# ADC_AH.net
KiCad netlist of a schematic drawn in Altium Designer
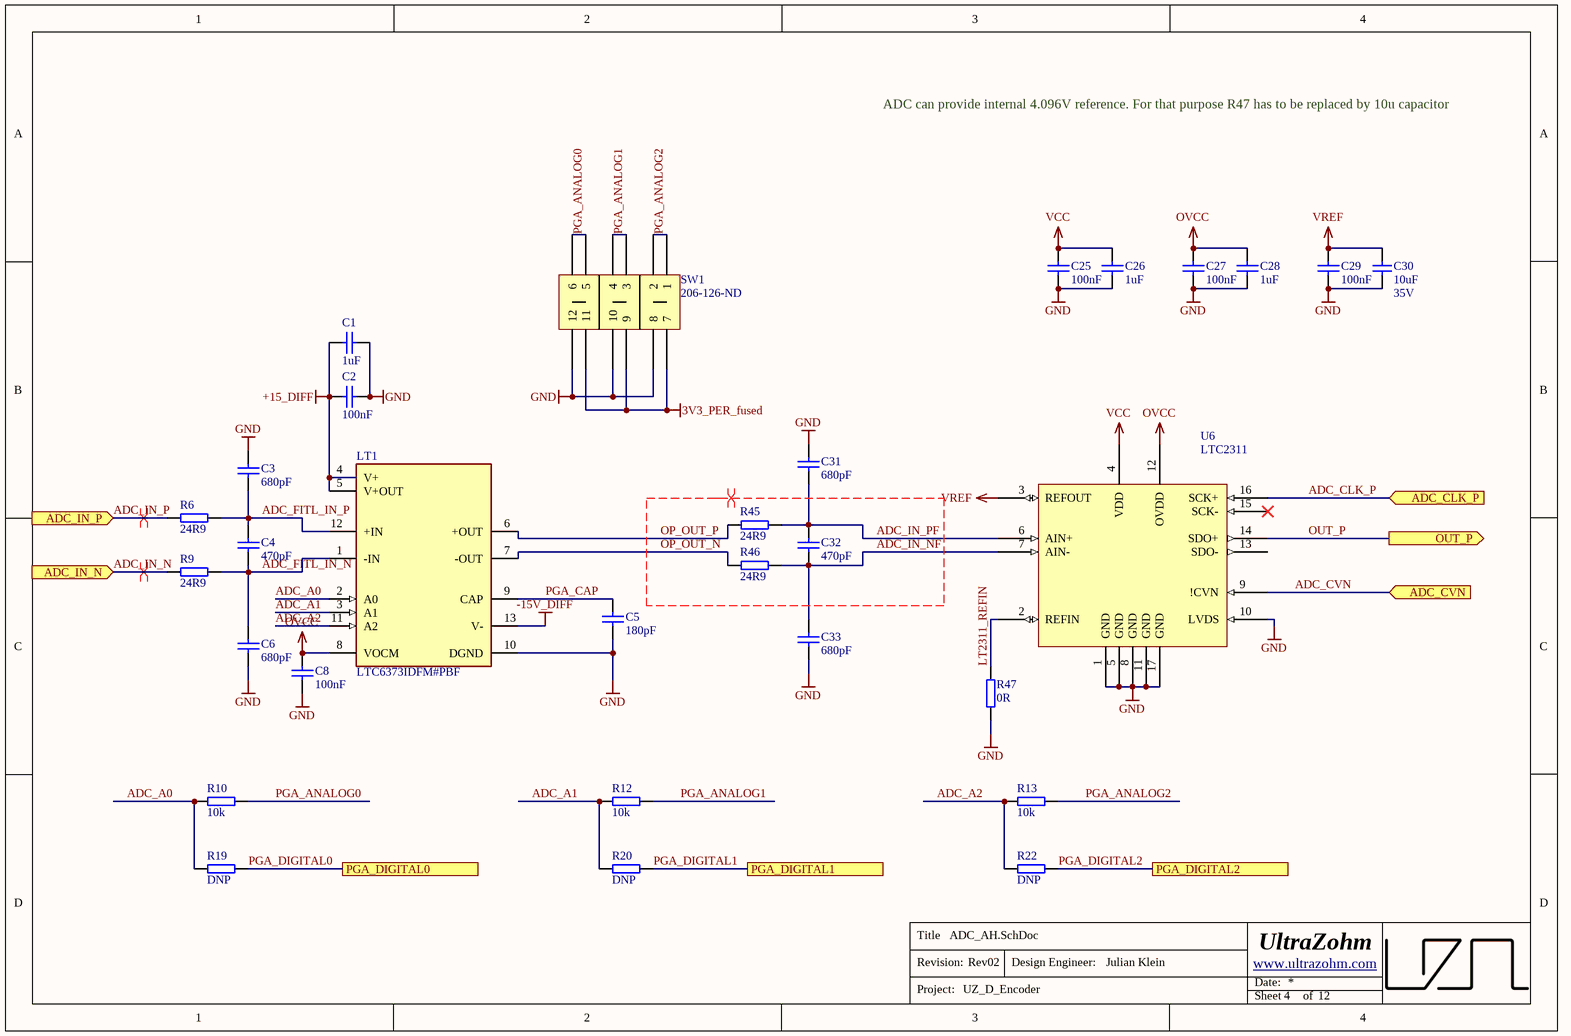
[diagram p0: ADC_AH.SchDoc]

(export (version "E")
  (design (tool "Eeschema 10.0.6"))
  (components
    (comp (ref "C1")
      (value "1uF")
      (footprint "CAPC1608X07N")
      (fields (field (name "MPN") "C0603C105K3R") (field (name "VOLTAGE") "25V"))
      (libsource (lib "UltraZohm_ADC") (part "Cap_0603"))
    )
    (comp (ref "C2")
      (value "100nF")
      (footprint "CAPC1608X07N")
      (fields (field (name "MF") "Würth") (field (name "MPN") "885012206071") (field (name "VOLTAGE") "25V"))
      (libsource (lib "UltraZohm_ADC") (part "Cap_0603"))
    )
    (comp (ref "C3")
      (value "680pF")
      (footprint "CAPC1608X07N")
      (fields
        (field (name "MF") "Vishay")
        (field (name "MPN") "VJ0603A681GXJCW1BC")
        (field (name "VOLTAGE") "16V")
      )
      (libsource (lib "UltraZohm_ADC") (part "Cap_0603"))
    )
    (comp (ref "C4")
      (value "470pF")
      (footprint "CAPC1608X07N")
      (fields
        (field (name "MF") "Vishay")
        (field (name "MPN") "VJ0603A471GXJPW1BC")
        (field (name "VOLTAGE") "16V")
      )
      (libsource (lib "UltraZohm_ADC") (part "Cap_0603"))
    )
    (comp (ref "C5")
      (value "180pF")
      (footprint "CAPC1608X07N")
      (fields
        (field (name "MF") "Vishay")
        (field (name "MPN") "VJ0603A681GXJCW1BC")
        (field (name "VOLTAGE") "16V")
      )
      (libsource (lib "UltraZohm_ADC") (part "Cap_0603"))
    )
    (comp (ref "C6")
      (value "680pF")
      (footprint "CAPC1608X07N")
      (fields
        (field (name "MF") "Vishay")
        (field (name "MPN") "VJ0603A681GXJCW1BC")
        (field (name "VOLTAGE") "16V")
      )
      (libsource (lib "UltraZohm_ADC") (part "Cap_0603"))
    )
    (comp (ref "C8")
      (value "100nF")
      (footprint "CAPC1608X07N")
      (fields (field (name "MF") "Würth") (field (name "MPN") "885012206071") (field (name "VOLTAGE") "25V"))
      (libsource (lib "UltraZohm_ADC") (part "Cap_0603"))
    )
    (comp (ref "C25")
      (value "100nF")
      (footprint "CAPC1608X07N")
      (fields (field (name "MF") "Würth") (field (name "MPN") "885012206071") (field (name "VOLTAGE") "25V"))
      (libsource (lib "UltraZohm_ADC") (part "Cap_0603"))
    )
    (comp (ref "C26")
      (value "1uF")
      (footprint "CAPC1608X07N")
      (fields (field (name "MPN") "C0603C105K3R") (field (name "VOLTAGE") "25V"))
      (libsource (lib "UltraZohm_ADC") (part "Cap_0603"))
    )
    (comp (ref "C27")
      (value "100nF")
      (footprint "CAPC1608X07N")
      (fields (field (name "MF") "Würth") (field (name "MPN") "885012206071") (field (name "VOLTAGE") "25V"))
      (libsource (lib "UltraZohm_ADC") (part "Cap_0603"))
    )
    (comp (ref "C28")
      (value "1uF")
      (footprint "CAPC1608X07N")
      (fields (field (name "MPN") "C0603C105K3R") (field (name "VOLTAGE") "25V"))
      (libsource (lib "UltraZohm_ADC") (part "Cap_0603"))
    )
    (comp (ref "C29")
      (value "100nF")
      (footprint "CAPC1608X07N")
      (fields (field (name "MF") "Würth") (field (name "MPN") "885012206071") (field (name "VOLTAGE") "25V"))
      (libsource (lib "UltraZohm_ADC") (part "Cap_0603"))
    )
    (comp (ref "C30")
      (value "10uF")
      (footprint "C_1206")
      (description "Capacitor 1206")
      (fields
        (field (name "TOLERANCE") "10%")
        (field (name "MF") "Murata Electronics")
        (field (name "VOLTAGE") "35V")
        (field (name "CREATED") "2018_06_25_AGeiger")
      )
      (libsource (lib "UltraZohm_ADC") (part "C_1206"))
    )
    (comp (ref "C31")
      (value "680pF")
      (footprint "CAPC1608X07N")
      (fields
        (field (name "MF") "Vishay")
        (field (name "MPN") "VJ0603A681GXJCW1BC")
        (field (name "VOLTAGE") "16V")
      )
      (libsource (lib "UltraZohm_ADC") (part "Cap_0603"))
    )
    (comp (ref "C32")
      (value "470pF")
      (footprint "CAPC1608X07N")
      (fields
        (field (name "MF") "Vishay")
        (field (name "MPN") "VJ0603A471GXJPW1BC")
        (field (name "VOLTAGE") "16V")
      )
      (libsource (lib "UltraZohm_ADC") (part "Cap_0603"))
    )
    (comp (ref "C33")
      (value "680pF")
      (footprint "CAPC1608X07N")
      (fields
        (field (name "MF") "Vishay")
        (field (name "MPN") "VJ0603A681GXJCW1BC")
        (field (name "VOLTAGE") "16V")
      )
      (libsource (lib "UltraZohm_ADC") (part "Cap_0603"))
    )
    (comp (ref "LT1")
      (value "LTC6373IDFM#PBF")
      (footprint "FP-LTC6373IDFM#PBF-MFG")
      (description "INST Amp Single ±18V 12-Pin DFN EP Tube")
      (libsource (lib "Altium Content Vault") (part "8e72af7b36638ae68c50ab628123914"))
    )
    (comp (ref "R6")
      (value "24R9")
      (footprint "RESC1608X06N")
      (fields (field (name "MF") "Yageo") (field (name "MPN") "RC0603FR-0724R9L"))
      (libsource (lib "UltraZohm_ADC") (part "R_0603"))
    )
    (comp (ref "R9")
      (value "24R9")
      (footprint "RESC1608X06N")
      (fields (field (name "MF") "Yageo") (field (name "MPN") "RC0603FR-0724R9L"))
      (libsource (lib "UltraZohm_ADC") (part "R_0603"))
    )
    (comp (ref "R10")
      (value "10k")
      (footprint "RESC1608X06N")
      (fields (field (name "MF") "Vishay") (field (name "MPN") "CRCW06030000Z0EAC"))
      (libsource (lib "UltraZohm_ADC") (part "R_0603"))
    )
    (comp (ref "R12")
      (value "10k")
      (footprint "RESC1608X06N")
      (fields (field (name "MF") "Vishay") (field (name "MPN") "CRCW06030000Z0EAC"))
      (libsource (lib "UltraZohm_ADC") (part "R_0603"))
    )
    (comp (ref "R13")
      (value "10k")
      (footprint "RESC1608X06N")
      (fields (field (name "MF") "Vishay") (field (name "MPN") "CRCW06030000Z0EAC"))
      (libsource (lib "UltraZohm_ADC") (part "R_0603"))
    )
    (comp (ref "R19")
      (value "DNP")
      (footprint "RESC1608X06N")
      (fields (field (name "MF") "Vishay") (field (name "MPN") "CRCW06030000Z0EAC"))
      (libsource (lib "UltraZohm_ADC") (part "R_0603"))
    )
    (comp (ref "R20")
      (value "DNP")
      (footprint "RESC1608X06N")
      (fields (field (name "MF") "Vishay") (field (name "MPN") "CRCW06030000Z0EAC"))
      (libsource (lib "UltraZohm_ADC") (part "R_0603"))
    )
    (comp (ref "R22")
      (value "DNP")
      (footprint "RESC1608X06N")
      (fields (field (name "MF") "Vishay") (field (name "MPN") "CRCW06030000Z0EAC"))
      (libsource (lib "UltraZohm_ADC") (part "R_0603"))
    )
    (comp (ref "R45")
      (value "24R9")
      (footprint "RESC1608X06N")
      (fields (field (name "MF") "Yageo") (field (name "MPN") "RC0603FR-0724R9L"))
      (libsource (lib "UltraZohm_ADC") (part "R_0603"))
    )
    (comp (ref "R46")
      (value "24R9")
      (footprint "RESC1608X06N")
      (fields (field (name "MF") "Yageo") (field (name "MPN") "RC0603FR-0724R9L"))
      (libsource (lib "UltraZohm_ADC") (part "R_0603"))
    )
    (comp (ref "R47")
      (value "0R")
      (footprint "RESC1608X06N")
      (fields (field (name "MF") "Vishay") (field (name "MPN") "CRCW06030000Z0EAC"))
      (libsource (lib "UltraZohm_ADC") (part "R_0603"))
    )
    (comp (ref "SW1")
      (value "206-126")
      (footprint "206-123")
      (description "Switch DIP OFF ON SPDT 6 Raised Slide 0.05A 24VDC PC Pins 2.54mm Thru-Hole Tube")
      (fields (field (name "MANUFACTURER") "CTS") (field (name "SUPPLIER PART NUMBER 1") "206-126-ND"))
      (libsource (lib "uz_d_encoder_lib") (part "206-126"))
    )
    (comp (ref "U6")
      (value "LTC2311")
      (footprint "LTC2311-16")
      (description "16 Bit SAR ADC, 5MSps")
      (fields (field (name "MF") "Analog Devices") (field (name "MPN") "LTC2311CMSE-16#PBF"))
      (libsource (lib "UltraZohm_ADC") (part "LTC2311-16"))
    )
  )
  (nets
    (net (code "1") (name "+15_DIFF") (class "Default")
      (node (ref "C1") (pin "1") (pinfunction "1_1") (pintype "passive"))
      (node (ref "C2") (pin "1") (pinfunction "1_1") (pintype "passive"))
      (node (ref "LT1") (pin "4") (pinfunction "V+_4") (pintype "power_in"))
      (node (ref "LT1") (pin "5") (pinfunction "V+OUT_5") (pintype "power_in"))
    )
    (net (code "2") (name "-15V_DIFF") (class "Default")
      (node (ref "LT1") (pin "13") (pinfunction "V-_13") (pintype "power_in"))
    )
    (net (code "3") (name "/ADC_A0") (class "Default")
      (node (ref "LT1") (pin "2") (pinfunction "A0_2") (pintype "input"))
      (node (ref "R10") (pin "2") (pintype "passive"))
      (node (ref "R19") (pin "2") (pintype "passive"))
    )
    (net (code "4") (name "/ADC_A1") (class "Default")
      (node (ref "LT1") (pin "3") (pinfunction "A1_3") (pintype "input"))
      (node (ref "R12") (pin "2") (pintype "passive"))
      (node (ref "R20") (pin "2") (pintype "passive"))
    )
    (net (code "5") (name "/ADC_A2") (class "Default")
      (node (ref "LT1") (pin "11") (pinfunction "A2_11") (pintype "input"))
      (node (ref "R13") (pin "2") (pintype "passive"))
      (node (ref "R22") (pin "2") (pintype "passive"))
    )
    (net (code "6") (name "/ADC_CLK_P") (class "Default")
      (node (ref "U6") (pin "16") (pinfunction "SCK+_16") (pintype "input"))
    )
    (net (code "7") (name "/ADC_CVN") (class "Default")
      (node (ref "U6") (pin "9") (pinfunction "!CVN_9") (pintype "input"))
    )
    (net (code "8") (name "/ADC_FITL_IN_N") (class "Default")
      (node (ref "C4") (pin "2") (pinfunction "2_2") (pintype "passive"))
      (node (ref "C6") (pin "1") (pinfunction "1_1") (pintype "passive"))
      (node (ref "LT1") (pin "1") (pinfunction "-IN_1") (pintype "tri_state"))
      (node (ref "R9") (pin "2") (pintype "passive"))
    )
    (net (code "9") (name "/ADC_FITL_IN_P") (class "Default")
      (node (ref "C3") (pin "2") (pinfunction "2_2") (pintype "passive"))
      (node (ref "C4") (pin "1") (pinfunction "1_1") (pintype "passive"))
      (node (ref "LT1") (pin "12") (pinfunction "+IN_12") (pintype "tri_state"))
      (node (ref "R6") (pin "2") (pintype "passive"))
    )
    (net (code "10") (name "/ADC_IN_N") (class "Default") (node (ref "R9") (pin "1") (pintype "passive")))
    (net (code "11") (name "/ADC_IN_NF") (class "Default")
      (node (ref "C32") (pin "2") (pinfunction "2_2") (pintype "passive"))
      (node (ref "C33") (pin "1") (pinfunction "1_1") (pintype "passive"))
      (node (ref "R46") (pin "2") (pintype "passive"))
      (node (ref "U6") (pin "7") (pinfunction "AIN-_7") (pintype "input"))
    )
    (net (code "12") (name "/ADC_IN_P") (class "Default") (node (ref "R6") (pin "1") (pintype "passive")))
    (net (code "13") (name "/ADC_IN_PF") (class "Default")
      (node (ref "C31") (pin "2") (pinfunction "2_2") (pintype "passive"))
      (node (ref "C32") (pin "1") (pinfunction "1_1") (pintype "passive"))
      (node (ref "R45") (pin "2") (pintype "passive"))
      (node (ref "U6") (pin "6") (pinfunction "AIN+_6") (pintype "input"))
    )
    (net (code "14") (name "/LT2311_REFIN") (class "Default")
      (node (ref "R47") (pin "2") (pintype "passive"))
      (node (ref "U6") (pin "2") (pinfunction "REFIN_2") (pintype "bidirectional"))
    )
    (net (code "15") (name "/OP_OUT_N") (class "Default")
      (node (ref "LT1") (pin "7") (pinfunction "-OUT_7") (pintype "passive"))
      (node (ref "R46") (pin "1") (pintype "passive"))
    )
    (net (code "16") (name "/OP_OUT_P") (class "Default")
      (node (ref "LT1") (pin "6") (pinfunction "+OUT_6") (pintype "passive"))
      (node (ref "R45") (pin "1") (pintype "passive"))
    )
    (net (code "17") (name "/OUT_P") (class "Default")
      (node (ref "U6") (pin "14") (pinfunction "SDO+_14") (pintype "output"))
    )
    (net (code "18") (name "/PGA_ANALOG0") (class "Default")
      (node (ref "R10") (pin "1") (pintype "passive"))
      (node (ref "SW1") (pin "5") (pinfunction "5_5") (pintype "passive"))
      (node (ref "SW1") (pin "6") (pinfunction "6_6") (pintype "passive"))
    )
    (net (code "19") (name "/PGA_ANALOG1") (class "Default")
      (node (ref "R12") (pin "1") (pintype "passive"))
      (node (ref "SW1") (pin "3") (pinfunction "3_3") (pintype "passive"))
      (node (ref "SW1") (pin "4") (pinfunction "4_4") (pintype "passive"))
    )
    (net (code "20") (name "/PGA_ANALOG2") (class "Default")
      (node (ref "R13") (pin "1") (pintype "passive"))
      (node (ref "SW1") (pin "1") (pinfunction "1_1") (pintype "passive"))
      (node (ref "SW1") (pin "2") (pinfunction "2_2") (pintype "passive"))
    )
    (net (code "21") (name "/PGA_CAP") (class "Default")
      (node (ref "C5") (pin "1") (pinfunction "1_1") (pintype "passive"))
      (node (ref "LT1") (pin "9") (pinfunction "CAP_9") (pintype "passive"))
    )
    (net (code "22") (name "/PGA_DIGITAL0") (class "Default")
      (node (ref "R19") (pin "1") (pintype "passive"))
    )
    (net (code "23") (name "/PGA_DIGITAL1") (class "Default")
      (node (ref "R20") (pin "1") (pintype "passive"))
    )
    (net (code "24") (name "/PGA_DIGITAL2") (class "Default")
      (node (ref "R22") (pin "1") (pintype "passive"))
    )
    (net (code "25") (name "3V3_PER_fused") (class "Default")
      (node (ref "SW1") (pin "11") (pinfunction "11_11") (pintype "passive"))
      (node (ref "SW1") (pin "7") (pinfunction "7_7") (pintype "passive"))
      (node (ref "SW1") (pin "9") (pinfunction "9_9") (pintype "passive"))
    )
    (net (code "26") (name "GND") (class "Default")
      (node (ref "C1") (pin "2") (pinfunction "2_2") (pintype "passive"))
      (node (ref "C2") (pin "2") (pinfunction "2_2") (pintype "passive"))
      (node (ref "C25") (pin "2") (pinfunction "2_2") (pintype "passive"))
      (node (ref "C26") (pin "1") (pinfunction "1_1") (pintype "passive"))
      (node (ref "C27") (pin "2") (pinfunction "2_2") (pintype "passive"))
      (node (ref "C28") (pin "1") (pinfunction "1_1") (pintype "passive"))
      (node (ref "C29") (pin "2") (pinfunction "2_2") (pintype "passive"))
      (node (ref "C3") (pin "1") (pinfunction "1_1") (pintype "passive"))
      (node (ref "C30") (pin "1") (pinfunction "1_1") (pintype "passive"))
      (node (ref "C31") (pin "1") (pinfunction "1_1") (pintype "passive"))
      (node (ref "C33") (pin "2") (pinfunction "2_2") (pintype "passive"))
      (node (ref "C5") (pin "2") (pinfunction "2_2") (pintype "passive"))
      (node (ref "C6") (pin "2") (pinfunction "2_2") (pintype "passive"))
      (node (ref "C8") (pin "2") (pinfunction "2_2") (pintype "passive"))
      (node (ref "LT1") (pin "10") (pinfunction "DGND_10") (pintype "power_in"))
      (node (ref "R47") (pin "1") (pintype "passive"))
      (node (ref "SW1") (pin "10") (pinfunction "10_10") (pintype "passive"))
      (node (ref "SW1") (pin "12") (pinfunction "12_12") (pintype "passive"))
      (node (ref "SW1") (pin "8") (pinfunction "8_8") (pintype "passive"))
      (node (ref "U6") (pin "1") (pinfunction "GND_1") (pintype "power_in"))
      (node (ref "U6") (pin "10") (pinfunction "LVDS_10") (pintype "input"))
      (node (ref "U6") (pin "11") (pinfunction "GND_11") (pintype "power_in"))
      (node (ref "U6") (pin "17") (pinfunction "GND_17") (pintype "power_in"))
      (node (ref "U6") (pin "5") (pinfunction "GND_5") (pintype "power_in"))
      (node (ref "U6") (pin "8") (pinfunction "GND_8") (pintype "power_in"))
    )
    (net (code "27") (name "OVCC") (class "Default")
      (node (ref "C27") (pin "1") (pinfunction "1_1") (pintype "passive"))
      (node (ref "C28") (pin "2") (pinfunction "2_2") (pintype "passive"))
      (node (ref "C8") (pin "1") (pinfunction "1_1") (pintype "passive"))
      (node (ref "LT1") (pin "8") (pinfunction "VOCM_8") (pintype "passive"))
      (node (ref "U6") (pin "12") (pinfunction "OVDD_12") (pintype "power_in"))
    )
    (net (code "28") (name "VCC") (class "Default")
      (node (ref "C25") (pin "1") (pinfunction "1_1") (pintype "passive"))
      (node (ref "C26") (pin "2") (pinfunction "2_2") (pintype "passive"))
      (node (ref "U6") (pin "4") (pinfunction "VDD_4") (pintype "power_in"))
    )
    (net (code "29") (name "VREF") (class "Default")
      (node (ref "C29") (pin "1") (pinfunction "1_1") (pintype "passive"))
      (node (ref "C30") (pin "2") (pinfunction "2_2") (pintype "passive"))
      (node (ref "U6") (pin "3") (pinfunction "REFOUT_3") (pintype "bidirectional"))
    )
    (net (code "30") (name "unconnected-(U6-SCK--Pad15)") (class "Default")
      (node (ref "U6") (pin "15") (pinfunction "SCK-_15") (pintype "input+no_connect"))
    )
    (net (code "31") (name "unconnected-(U6-SDO--Pad13)") (class "Default")
      (node (ref "U6") (pin "13") (pinfunction "SDO-_13") (pintype "output"))
    )
  )
)
